# Toplevel.net
KiCad netlist of a schematic drawn in Altium Designer
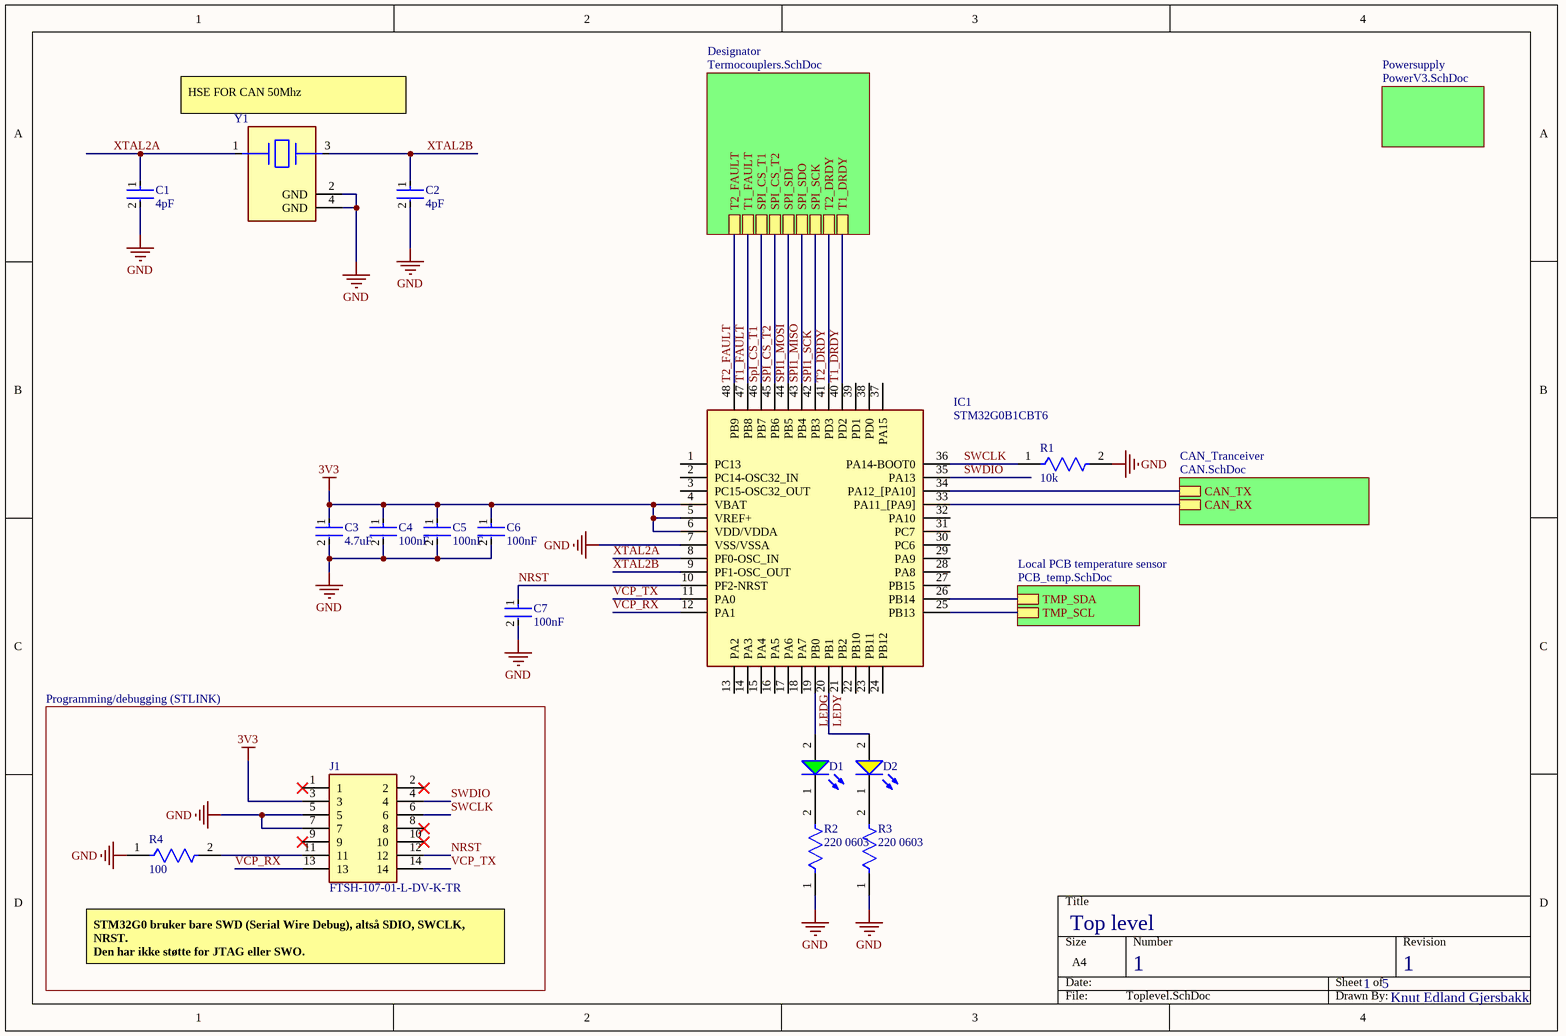
[diagram p0: Toplevel.SchDoc]

(export (version "E")
  (design (tool "Eeschema 10.0.6"))
  (components
    (comp (ref "C1")
      (value "4pF")
      (footprint "FP-GQM187-0_15-IPC_B")
      (description "GQM1875C2E4R0BB12D\r\nCeramic Capacitor 4pF ±0.1pF 250VDC C0G 0603 Paper T/R")
      (libsource (lib "Altium Content Vault") (part "02cd4be3c70576c341d710602a673aa"))
    )
    (comp (ref "C2")
      (value "4pF")
      (footprint "FP-GQM187-0_15-IPC_B")
      (description "GQM1875C2E4R0BB12D\r\nCeramic Capacitor 4pF ±0.1pF 250VDC C0G 0603 Paper T/R")
      (libsource (lib "Altium Content Vault") (part "02cd4be3c70576c341d710602a673aa"))
    )
    (comp (ref "C3")
      (value "4.7uF")
      (footprint "FP-GCM21B-0_15-IPC_A")
      (description "Ceramic Capacitor for Automotive 4.7uF ±10% 16VDC X7R 0805 Embossed T/R")
      (fields (field (name "TOLERANCE") "10%") (field (name "VOLTAGE") "16V"))
      (libsource (lib "Altium Content Vault") (part "02cd4be3c70576c341d710602a673aa"))
    )
    (comp (ref "C4")
      (value "100nF")
      (footprint "FP-CL10-IPC_A")
      (description "Cap Ceramic 100nF 16V X7R ±10% Pad SMD 0603 +125°C T/R")
      (fields (field (name "TOLERANCE") "10%"))
      (libsource (lib "Altium Content Vault") (part "b4654b650e69147ec39a6b967a45e02"))
    )
    (comp (ref "C5")
      (value "100nF")
      (footprint "FP-CL10-IPC_A")
      (description "Cap Ceramic 100nF 16V X7R ±10% Pad SMD 0603 +125°C T/R")
      (fields (field (name "TOLERANCE") "10%"))
      (libsource (lib "Altium Content Vault") (part "b4654b650e69147ec39a6b967a45e02"))
    )
    (comp (ref "C6")
      (value "100nF")
      (footprint "FP-CL10-IPC_A")
      (description "Cap Ceramic 100nF 16V X7R ±10% Pad SMD 0603 +125°C T/R")
      (fields (field (name "TOLERANCE") "10%"))
      (libsource (lib "Altium Content Vault") (part "b4654b650e69147ec39a6b967a45e02"))
    )
    (comp (ref "C7")
      (value "100nF")
      (footprint "FP-CL10-IPC_A")
      (description "Cap Ceramic 100nF 16V X7R ±10% Pad SMD 0603 +125°C T/R")
      (fields (field (name "TOLERANCE") "10%"))
      (libsource (lib "Altium Content Vault") (part "b4654b650e69147ec39a6b967a45e02"))
    )
    (comp (ref "D1")
      (value "150060GS55040")
      (footprint "WL-SMCD_0603")
      (description "150060GS55040 WL-SMCD SMT Mono-color Chip LED Diffused")
      (libsource (lib "Altium Content Vault") (part "LED_Green_2A-1K"))
    )
    (comp (ref "D2")
      (value "150060YS75020")
      (footprint "WL-SMCW_0603_150060xx75020")
      (description "WL-SMCW SMT Mono-Color Chip LED Waterclear super f")
      (libsource (lib "Altium Content Vault") (part "LED_Yellow_2A-1K"))
    )
    (comp (ref "IC1")
      (value "STM32G0B1CBT6")
      (footprint "SamacSys:QFP50P900X900X160-48N")
      (description "Integrated Circuit")
      (fields (field (name "MOUSER PART NUMBER") "511-STM32G0B1CBT6"))
      (libsource (lib "*") (part "STM32G0B1CBT6"))
    )
    (comp (ref "J1")
      (value "FTSH-107-01-L-DV-K-TR")
      (footprint "SamacSys:FTSH10701LDVKTR")
      (description "Connector")
      (fields (field (name "MOUSER PART NUMBER") "200-FTSH10701LDVKTR"))
      (libsource (lib "*") (part "FTSH-107-01-L-DV-K-TR"))
    )
    (comp (ref "R1")
      (value "10k")
      (footprint "FP-RT0603-IPC_C")
      (description "RES SMD 10K OHM 1% 1/10W 0603\r\nRT0603FRE0710KL")
      (fields
        (field (name "MANUFACTURER") "Yageo")
        (field (name "OCTOPART") "https://octopart.com/rt0603fre0710kl-yageo-40009243")
      )
      (libsource (lib "Altium Content Vault") (part "1029c3af85768c4190bb7ad29bc67b5"))
    )
    (comp (ref "R2")
      (value "220 0603")
      (footprint "FP-AF0603-IPC_C")
      (description "AF0603JR-07220RL Anti-Sulfurated Chip Resistors Automotive Grade 220Ω 5% 100ppm/°C 0603")
      (fields (field (name "TOLERANCE") "5%"))
      (libsource (lib "Altium Content Vault") (part "1029c3af85768c4190bb7ad29bc67b5"))
    )
    (comp (ref "R3")
      (value "220 0603")
      (footprint "FP-AF0603-IPC_C")
      (description "AF0603JR-07220RL Anti-Sulfurated Chip Resistors Automotive Grade 220Ω 5% 100ppm/°C 0603")
      (fields (field (name "TOLERANCE") "5%"))
      (libsource (lib "Altium Content Vault") (part "1029c3af85768c4190bb7ad29bc67b5"))
    )
    (comp (ref "R4")
      (value "100")
      (footprint "FP-RT0603-MFG")
      (description "RT0603 100Ω 0.1W 50 ppm/°C 1.00% RT0603FRE07100RL")
      (fields
        (field (name "OCTOPART") "https://octopart.com/rt0603fre10100rl-yageo-22252409")
        (field (name "TOLERANCE") "0.01")
      )
      (libsource (lib "Altium Content Vault") (part "1029c3af85768c4190bb7ad29bc67b5"))
    )
    (comp (ref "Y1")
      (value "ABM10W-50.0000MHZ-4-B1U-T3")
      (footprint "FP-ABM10W-MFG")
      (description "Crystal 50MHz ±10ppm 4pF SMD-4 2.5mm x 2mm")
      (libsource (lib "Altium Content Vault") (part "5d53a81b36bb19e40e9e80ec3e46f97"))
    )
  )
  (nets
    (net (code "1") (name "/CAN_RX") (class "Default")
      (node (ref "IC1") (pin "33") (pinfunction "PA11_[PA9]_33") (pintype "passive"))
    )
    (net (code "2") (name "/CAN_TX") (class "Default")
      (node (ref "IC1") (pin "34") (pinfunction "PA12_[PA10]_34") (pintype "passive"))
    )
    (net (code "3") (name "/LEDG") (class "Default")
      (node (ref "D1") (pin "2") (pinfunction "A_2") (pintype "passive"))
      (node (ref "IC1") (pin "19") (pinfunction "PB0_19") (pintype "passive"))
    )
    (net (code "4") (name "/LEDY") (class "Default")
      (node (ref "D2") (pin "2") (pinfunction "A_2") (pintype "passive"))
      (node (ref "IC1") (pin "20") (pinfunction "PB1_20") (pintype "passive"))
    )
    (net (code "5") (name "/NRST") (class "Default")
      (node (ref "C7") (pin "1") (pinfunction "1_1") (pintype "passive"))
      (node (ref "IC1") (pin "10") (pinfunction "PF2-NRST_10") (pintype "passive"))
      (node (ref "J1") (pin "12") (pinfunction "12_12") (pintype "passive"))
    )
    (net (code "6") (name "/SPI1_MISO") (class "Default")
      (node (ref "IC1") (pin "43") (pinfunction "PB4_43") (pintype "passive"))
    )
    (net (code "7") (name "/SPI1_MOSI") (class "Default")
      (node (ref "IC1") (pin "44") (pinfunction "PB5_44") (pintype "passive"))
    )
    (net (code "8") (name "/SPI1_SCK") (class "Default")
      (node (ref "IC1") (pin "42") (pinfunction "PB3_42") (pintype "passive"))
    )
    (net (code "9") (name "/SPI_CS_T2") (class "Default")
      (node (ref "IC1") (pin "45") (pinfunction "PB6_45") (pintype "passive"))
    )
    (net (code "10") (name "/SWCLK") (class "Default")
      (node (ref "IC1") (pin "36") (pinfunction "PA14-BOOT0_36") (pintype "passive"))
      (node (ref "J1") (pin "6") (pinfunction "6_6") (pintype "passive"))
      (node (ref "R1") (pin "1") (pinfunction "1_1") (pintype "passive"))
    )
    (net (code "11") (name "/SWDIO") (class "Default")
      (node (ref "IC1") (pin "35") (pinfunction "PA13_35") (pintype "passive"))
      (node (ref "J1") (pin "4") (pinfunction "4_4") (pintype "passive"))
    )
    (net (code "12") (name "/SpI_CS_T1") (class "Default")
      (node (ref "IC1") (pin "46") (pinfunction "PB7_46") (pintype "passive"))
    )
    (net (code "13") (name "/T1_DRDY") (class "Default")
      (node (ref "IC1") (pin "40") (pinfunction "PD2_40") (pintype "passive"))
    )
    (net (code "14") (name "/T1_FAULT") (class "Default")
      (node (ref "IC1") (pin "47") (pinfunction "PB8_47") (pintype "passive"))
    )
    (net (code "15") (name "/T2_DRDY") (class "Default")
      (node (ref "IC1") (pin "41") (pinfunction "PD3_41") (pintype "passive"))
    )
    (net (code "16") (name "/T2_FAULT") (class "Default")
      (node (ref "IC1") (pin "48") (pinfunction "PB9_48") (pintype "passive"))
    )
    (net (code "17") (name "/TMP_SCL") (class "Default")
      (node (ref "IC1") (pin "25") (pinfunction "PB13_25") (pintype "passive"))
    )
    (net (code "18") (name "/TMP_SDA") (class "Default")
      (node (ref "IC1") (pin "26") (pinfunction "PB14_26") (pintype "passive"))
    )
    (net (code "19") (name "/VCP_RX") (class "Default")
      (node (ref "IC1") (pin "12") (pinfunction "PA1_12") (pintype "passive"))
      (node (ref "J1") (pin "13") (pinfunction "13_13") (pintype "passive"))
    )
    (net (code "20") (name "/VCP_TX") (class "Default")
      (node (ref "IC1") (pin "11") (pinfunction "PA0_11") (pintype "passive"))
      (node (ref "J1") (pin "14") (pinfunction "14_14") (pintype "passive"))
    )
    (net (code "21") (name "/XTAL2A") (class "Default")
      (node (ref "C1") (pin "1") (pinfunction "1_1") (pintype "passive"))
      (node (ref "IC1") (pin "8") (pinfunction "PF0-OSC_IN_8") (pintype "passive"))
      (node (ref "Y1") (pin "1") (pinfunction "1_1") (pintype "passive"))
    )
    (net (code "22") (name "/XTAL2B") (class "Default")
      (node (ref "C2") (pin "1") (pinfunction "1_1") (pintype "passive"))
      (node (ref "IC1") (pin "9") (pinfunction "PF1-OSC_OUT_9") (pintype "passive"))
      (node (ref "Y1") (pin "3") (pinfunction "3_3") (pintype "passive"))
    )
    (net (code "23") (name "3V3") (class "Default")
      (node (ref "C3") (pin "1") (pinfunction "1_1") (pintype "passive"))
      (node (ref "C4") (pin "1") (pinfunction "1_1") (pintype "passive"))
      (node (ref "C5") (pin "1") (pinfunction "1_1") (pintype "passive"))
      (node (ref "C6") (pin "1") (pinfunction "1_1") (pintype "passive"))
      (node (ref "IC1") (pin "4") (pinfunction "VBAT_4") (pintype "passive"))
      (node (ref "IC1") (pin "5") (pinfunction "VREF+_5") (pintype "passive"))
      (node (ref "IC1") (pin "6") (pinfunction "VDD/VDDA_6") (pintype "passive"))
      (node (ref "J1") (pin "3") (pinfunction "3_3") (pintype "passive"))
    )
    (net (code "24") (name "GND") (class "Default")
      (node (ref "C1") (pin "2") (pinfunction "2_2") (pintype "passive"))
      (node (ref "C2") (pin "2") (pinfunction "2_2") (pintype "passive"))
      (node (ref "C3") (pin "2") (pinfunction "2_2") (pintype "passive"))
      (node (ref "C4") (pin "2") (pinfunction "2_2") (pintype "passive"))
      (node (ref "C5") (pin "2") (pinfunction "2_2") (pintype "passive"))
      (node (ref "C6") (pin "2") (pinfunction "2_2") (pintype "passive"))
      (node (ref "C7") (pin "2") (pinfunction "2_2") (pintype "passive"))
      (node (ref "IC1") (pin "7") (pinfunction "VSS/VSSA_7") (pintype "passive"))
      (node (ref "J1") (pin "5") (pinfunction "5_5") (pintype "passive"))
      (node (ref "J1") (pin "7") (pinfunction "7_7") (pintype "passive"))
      (node (ref "R1") (pin "2") (pinfunction "2_2") (pintype "passive"))
      (node (ref "R2") (pin "1") (pinfunction "1_1") (pintype "passive"))
      (node (ref "R3") (pin "1") (pinfunction "1_1") (pintype "passive"))
      (node (ref "R4") (pin "1") (pinfunction "1_1") (pintype "passive"))
      (node (ref "Y1") (pin "2") (pinfunction "GND_2") (pintype "power_in"))
      (node (ref "Y1") (pin "4") (pinfunction "GND_4") (pintype "power_in"))
    )
    (net (code "25") (name "Net-(D1-K)") (class "Default")
      (node (ref "D1") (pin "1") (pinfunction "K_1") (pintype "passive"))
      (node (ref "R2") (pin "2") (pinfunction "2_2") (pintype "passive"))
    )
    (net (code "26") (name "Net-(D2-K)") (class "Default")
      (node (ref "D2") (pin "1") (pinfunction "K_1") (pintype "passive"))
      (node (ref "R3") (pin "2") (pinfunction "2_2") (pintype "passive"))
    )
    (net (code "27") (name "Net-(J1-Pad11)") (class "Default")
      (node (ref "J1") (pin "11") (pinfunction "11_11") (pintype "passive"))
      (node (ref "R4") (pin "2") (pinfunction "2_2") (pintype "passive"))
    )
    (net (code "28") (name "unconnected-(IC1-PA2-Pad13)") (class "Default")
      (node (ref "IC1") (pin "13") (pinfunction "PA2_13") (pintype "passive"))
    )
    (net (code "29") (name "unconnected-(IC1-PA3-Pad14)") (class "Default")
      (node (ref "IC1") (pin "14") (pinfunction "PA3_14") (pintype "passive"))
    )
    (net (code "30") (name "unconnected-(IC1-PA4-Pad15)") (class "Default")
      (node (ref "IC1") (pin "15") (pinfunction "PA4_15") (pintype "passive"))
    )
    (net (code "31") (name "unconnected-(IC1-PA5-Pad16)") (class "Default")
      (node (ref "IC1") (pin "16") (pinfunction "PA5_16") (pintype "passive"))
    )
    (net (code "32") (name "unconnected-(IC1-PA6-Pad17)") (class "Default")
      (node (ref "IC1") (pin "17") (pinfunction "PA6_17") (pintype "passive"))
    )
    (net (code "33") (name "unconnected-(IC1-PA7-Pad18)") (class "Default")
      (node (ref "IC1") (pin "18") (pinfunction "PA7_18") (pintype "passive"))
    )
    (net (code "34") (name "unconnected-(IC1-PA8-Pad28)") (class "Default")
      (node (ref "IC1") (pin "28") (pinfunction "PA8_28") (pintype "passive"))
    )
    (net (code "35") (name "unconnected-(IC1-PA9-Pad29)") (class "Default")
      (node (ref "IC1") (pin "29") (pinfunction "PA9_29") (pintype "passive"))
    )
    (net (code "36") (name "unconnected-(IC1-PA10-Pad32)") (class "Default")
      (node (ref "IC1") (pin "32") (pinfunction "PA10_32") (pintype "passive"))
    )
    (net (code "37") (name "unconnected-(IC1-PA15-Pad37)") (class "Default")
      (node (ref "IC1") (pin "37") (pinfunction "PA15_37") (pintype "passive"))
    )
    (net (code "38") (name "unconnected-(IC1-PB2-Pad21)") (class "Default")
      (node (ref "IC1") (pin "21") (pinfunction "PB2_21") (pintype "passive"))
    )
    (net (code "39") (name "unconnected-(IC1-PB10-Pad22)") (class "Default")
      (node (ref "IC1") (pin "22") (pinfunction "PB10_22") (pintype "passive"))
    )
    (net (code "40") (name "unconnected-(IC1-PB11-Pad23)") (class "Default")
      (node (ref "IC1") (pin "23") (pinfunction "PB11_23") (pintype "passive"))
    )
    (net (code "41") (name "unconnected-(IC1-PB12-Pad24)") (class "Default")
      (node (ref "IC1") (pin "24") (pinfunction "PB12_24") (pintype "passive"))
    )
    (net (code "42") (name "unconnected-(IC1-PB15-Pad27)") (class "Default")
      (node (ref "IC1") (pin "27") (pinfunction "PB15_27") (pintype "passive"))
    )
    (net (code "43") (name "unconnected-(IC1-PC6-Pad30)") (class "Default")
      (node (ref "IC1") (pin "30") (pinfunction "PC6_30") (pintype "passive"))
    )
    (net (code "44") (name "unconnected-(IC1-PC7-Pad31)") (class "Default")
      (node (ref "IC1") (pin "31") (pinfunction "PC7_31") (pintype "passive"))
    )
    (net (code "45") (name "unconnected-(IC1-PC13-Pad1)") (class "Default")
      (node (ref "IC1") (pin "1") (pinfunction "PC13_1") (pintype "passive"))
    )
    (net (code "46") (name "unconnected-(IC1-PC14-OSC32_IN-Pad2)") (class "Default")
      (node (ref "IC1") (pin "2") (pinfunction "PC14-OSC32_IN_2") (pintype "passive"))
    )
    (net (code "47") (name "unconnected-(IC1-PC15-OSC32_OUT-Pad3)") (class "Default")
      (node (ref "IC1") (pin "3") (pinfunction "PC15-OSC32_OUT_3") (pintype "passive"))
    )
    (net (code "48") (name "unconnected-(IC1-PD0-Pad38)") (class "Default")
      (node (ref "IC1") (pin "38") (pinfunction "PD0_38") (pintype "passive"))
    )
    (net (code "49") (name "unconnected-(IC1-PD1-Pad39)") (class "Default")
      (node (ref "IC1") (pin "39") (pinfunction "PD1_39") (pintype "passive"))
    )
    (net (code "50") (name "unconnected-(J1-Pad1)") (class "Default")
      (node (ref "J1") (pin "1") (pinfunction "1_1") (pintype "passive+no_connect"))
    )
    (net (code "51") (name "unconnected-(J1-Pad2)") (class "Default")
      (node (ref "J1") (pin "2") (pinfunction "2_2") (pintype "passive+no_connect"))
    )
    (net (code "52") (name "unconnected-(J1-Pad8)") (class "Default")
      (node (ref "J1") (pin "8") (pinfunction "8_8") (pintype "passive+no_connect"))
    )
    (net (code "53") (name "unconnected-(J1-Pad9)") (class "Default")
      (node (ref "J1") (pin "9") (pinfunction "9_9") (pintype "passive+no_connect"))
    )
    (net (code "54") (name "unconnected-(J1-Pad10)") (class "Default")
      (node (ref "J1") (pin "10") (pinfunction "10_10") (pintype "passive+no_connect"))
    )
  )
)
